# compare2.net
KiCad netlist of a schematic drawn in EAGLE
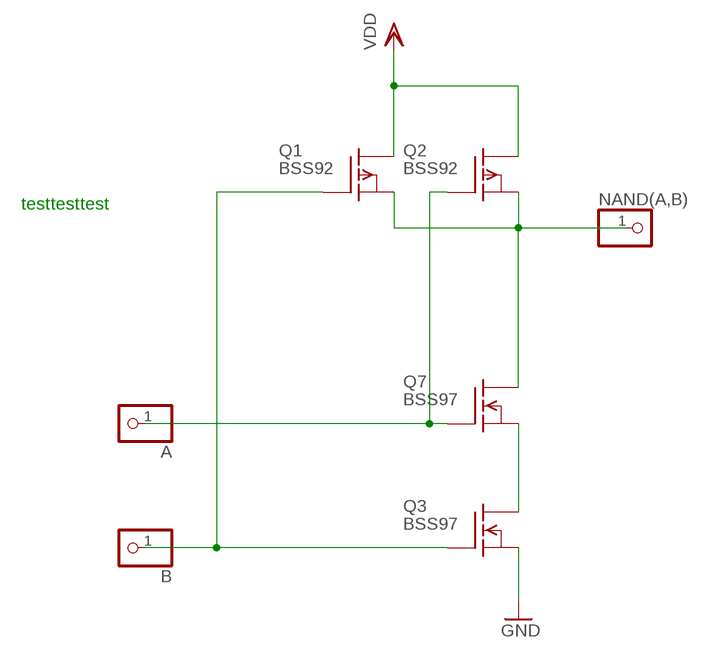
[diagram p0: schematic, sheet 1]

(export (version "E")
  (design (tool "Eeschema 10.0.6"))
  (components
    (comp (ref "A")
      (value "PINHD-1X1")
      (footprint "eagle-import:1X01")
      (libsource (lib "eagle-import") (part "PINHD-1X1"))
    )
    (comp (ref "B")
      (value "PINHD-1X1")
      (footprint "eagle-import:1X01")
      (libsource (lib "eagle-import") (part "PINHD-1X1"))
    )
    (comp (ref "NAND(A,B)")
      (value "PINHD-1X1")
      (footprint "eagle-import:1X01")
      (libsource (lib "eagle-import") (part "PINHD-1X1"))
    )
    (comp (ref "Q1")
      (value "BSS92")
      (footprint "eagle-import:TO92")
      (libsource (lib "eagle-import") (part "BSS92"))
    )
    (comp (ref "Q2")
      (value "BSS92")
      (footprint "eagle-import:TO92")
      (libsource (lib "eagle-import") (part "BSS92"))
    )
    (comp (ref "Q3")
      (value "BSS97")
      (footprint "eagle-import:TO202")
      (libsource (lib "eagle-import") (part "BSS97"))
    )
    (comp (ref "Q7")
      (value "BSS97")
      (footprint "eagle-import:TO202")
      (libsource (lib "eagle-import") (part "BSS97"))
    )
  )
  (nets
    (net (code "1") (name "GND") (class "Default")
      (node (ref "Q3") (pin "1") (pinfunction "S_1") (pintype "passive"))
    )
    (net (code "2") (name "Net-(Q1-G)") (class "Default")
      (node (ref "B") (pin "1") (pinfunction "1_1") (pintype "passive"))
      (node (ref "Q1") (pin "1") (pinfunction "G_1") (pintype "passive"))
      (node (ref "Q3") (pin "3") (pinfunction "G_3") (pintype "passive"))
    )
    (net (code "3") (name "Net-(Q1-S)") (class "Default")
      (node (ref "NAND(A,B)") (pin "1") (pinfunction "1_1") (pintype "passive"))
      (node (ref "Q1") (pin "3") (pinfunction "S_3") (pintype "passive"))
      (node (ref "Q2") (pin "3") (pinfunction "S_3") (pintype "passive"))
      (node (ref "Q7") (pin "2") (pinfunction "D_2") (pintype "passive"))
    )
    (net (code "4") (name "Net-(Q2-G)") (class "Default")
      (node (ref "A") (pin "1") (pinfunction "1_1") (pintype "passive"))
      (node (ref "Q2") (pin "1") (pinfunction "G_1") (pintype "passive"))
      (node (ref "Q7") (pin "3") (pinfunction "G_3") (pintype "passive"))
    )
    (net (code "5") (name "Net-(Q3-D)") (class "Default")
      (node (ref "Q3") (pin "2") (pinfunction "D_2") (pintype "passive"))
      (node (ref "Q7") (pin "1") (pinfunction "S_1") (pintype "passive"))
    )
    (net (code "6") (name "VDD") (class "Default")
      (node (ref "Q1") (pin "2") (pinfunction "D_2") (pintype "passive"))
      (node (ref "Q2") (pin "2") (pinfunction "D_2") (pintype "passive"))
    )
  )
)
